# FOC.net
KiCad netlist of a schematic drawn in Altium Designer
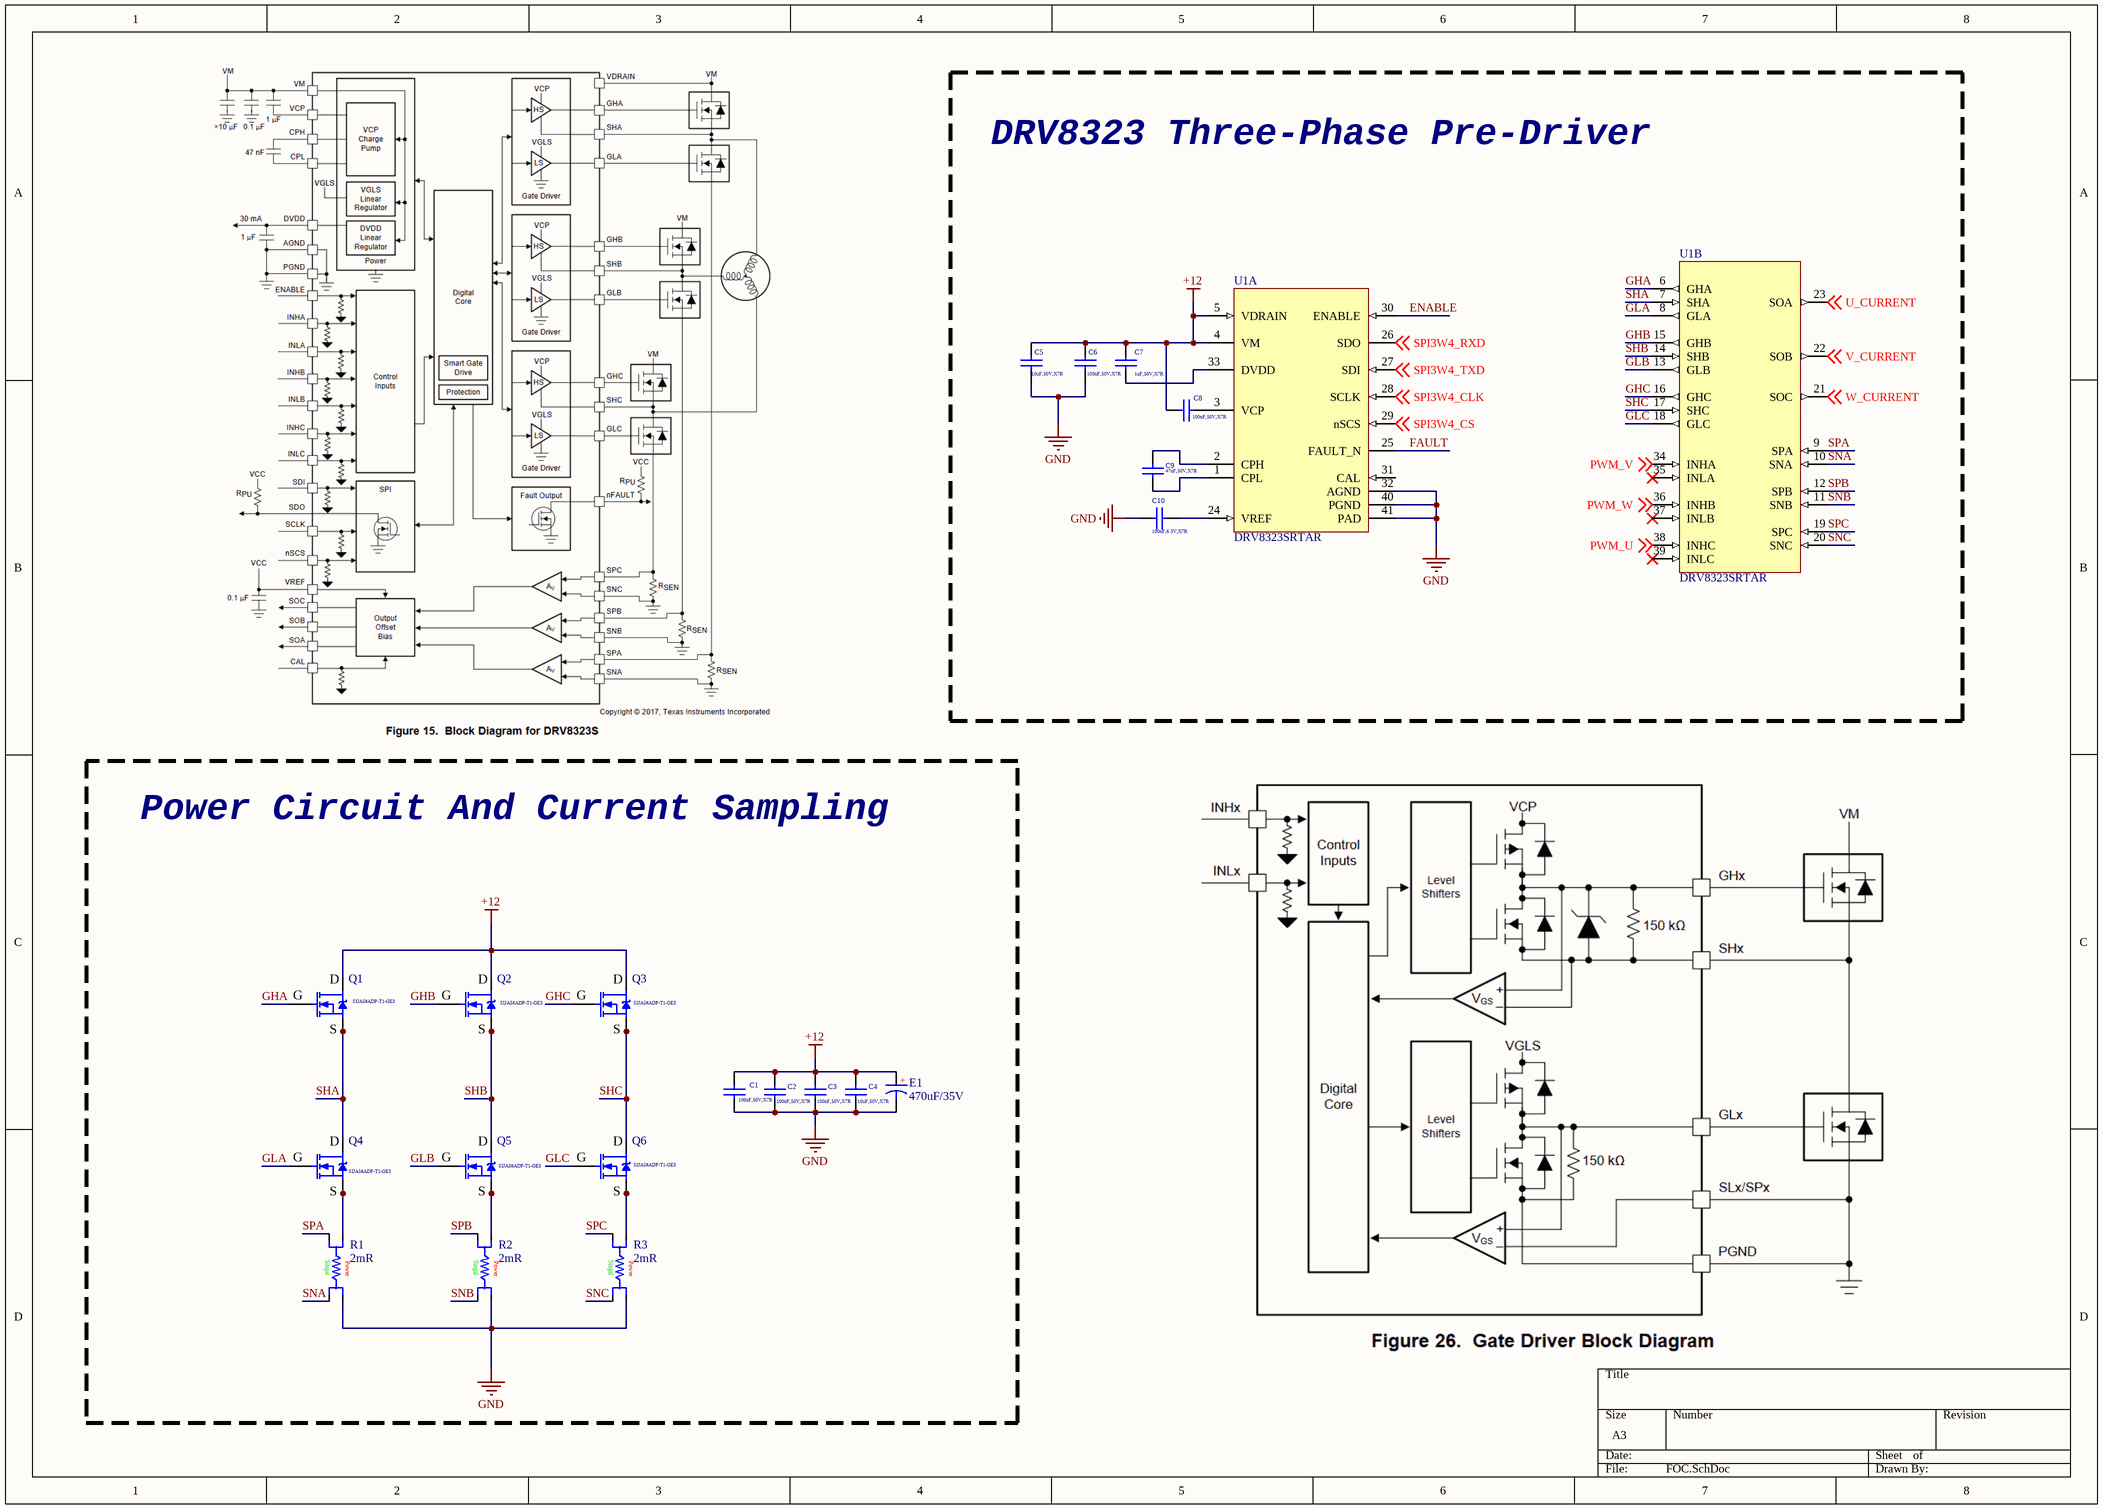
[diagram p0: FOC.SchDoc]

(export (version "E")
  (design (tool "Eeschema 10.0.6"))
  (components
    (comp (ref "C1")
      (value "100nF,50V,X7R")
      (footprint "C0603_L")
      (description "贴片电容/MLCC电容")
      (libsource (lib "0.1 - 电阻-电容-电感-保险丝-晶振-晶体-磁珠-电位器-法拉电容-馈通电容") (part "C"))
    )
    (comp (ref "C2")
      (value "100nF,50V,X7R")
      (footprint "C0603_L")
      (description "贴片电容/MLCC电容")
      (libsource (lib "0.1 - 电阻-电容-电感-保险丝-晶振-晶体-磁珠-电位器-法拉电容-馈通电容") (part "C"))
    )
    (comp (ref "C3")
      (value "100nF,50V,X7R")
      (footprint "C0603_L")
      (description "贴片电容/MLCC电容")
      (libsource (lib "0.1 - 电阻-电容-电感-保险丝-晶振-晶体-磁珠-电位器-法拉电容-馈通电容") (part "C"))
    )
    (comp (ref "C4")
      (value "10uF,50V,X7R")
      (footprint "C0603_L")
      (description "贴片电容/MLCC电容")
      (libsource (lib "0.1 - 电阻-电容-电感-保险丝-晶振-晶体-磁珠-电位器-法拉电容-馈通电容") (part "C"))
    )
    (comp (ref "C5")
      (value "10uF,50V,X7R")
      (footprint "C0402_L")
      (description "贴片电容/MLCC电容")
      (libsource (lib "0.1 - 电阻-电容-电感-保险丝-晶振-晶体-磁珠-电位器-法拉电容-馈通电容") (part "C"))
    )
    (comp (ref "C6")
      (value "100nF,50V,X7R")
      (footprint "C0402_L")
      (description "贴片电容/MLCC电容")
      (libsource (lib "0.1 - 电阻-电容-电感-保险丝-晶振-晶体-磁珠-电位器-法拉电容-馈通电容") (part "C"))
    )
    (comp (ref "C7")
      (value "1uF,50V,X7R")
      (footprint "C0402_L")
      (description "贴片电容/MLCC电容")
      (libsource (lib "0.1 - 电阻-电容-电感-保险丝-晶振-晶体-磁珠-电位器-法拉电容-馈通电容") (part "C"))
    )
    (comp (ref "C8")
      (value "100nF,50V,X7R")
      (footprint "C0402_L")
      (description "贴片电容/MLCC电容")
      (libsource (lib "0.1 - 电阻-电容-电感-保险丝-晶振-晶体-磁珠-电位器-法拉电容-馈通电容") (part "C"))
    )
    (comp (ref "C9")
      (value "47nF,50V,X7R")
      (footprint "C0402_L")
      (description "贴片电容/MLCC电容")
      (libsource (lib "0.1 - 电阻-电容-电感-保险丝-晶振-晶体-磁珠-电位器-法拉电容-馈通电容") (part "C"))
    )
    (comp (ref "C10")
      (value "100nF,6.3V,X7R")
      (footprint "C0402_L")
      (description "贴片电容/MLCC电容")
      (libsource (lib "0.1 - 电阻-电容-电感-保险丝-晶振-晶体-磁珠-电位器-法拉电容-馈通电容") (part "C"))
    )
    (comp (ref "E1")
      (value "470uF/35V")
      (footprint "CE E(8*6.2)")
      (description "贴片电解电容")
      (libsource (lib "0.1 - 电阻-电容-电感-保险丝-晶振-晶体-磁珠-电位器-法拉电容-馈通电容") (part "CE_SMD"))
    )
    (comp (ref "Q1")
      (value "SIJA58ADP-T1-GE3")
      (footprint "POWERPAK SO-8L_VIS")
      (description "Power Field-Effect Transistor")
      (libsource (lib "海南大学MECHA战队") (part "SIJA58ADP-T1-GE3"))
    )
    (comp (ref "Q2")
      (value "SIJA58ADP-T1-GE3")
      (footprint "POWERPAK SO-8L_VIS")
      (description "Power Field-Effect Transistor")
      (libsource (lib "海南大学MECHA战队") (part "SIJA58ADP-T1-GE3"))
    )
    (comp (ref "Q3")
      (value "SIJA58ADP-T1-GE3")
      (footprint "POWERPAK SO-8L_VIS")
      (description "Power Field-Effect Transistor")
      (libsource (lib "海南大学MECHA战队") (part "SIJA58ADP-T1-GE3"))
    )
    (comp (ref "Q4")
      (value "SIJA58ADP-T1-GE3")
      (footprint "POWERPAK SO-8L_VIS")
      (description "Power Field-Effect Transistor")
      (libsource (lib "海南大学MECHA战队") (part "SIJA58ADP-T1-GE3"))
    )
    (comp (ref "Q5")
      (value "SIJA58ADP-T1-GE3")
      (footprint "POWERPAK SO-8L_VIS")
      (description "Power Field-Effect Transistor")
      (libsource (lib "海南大学MECHA战队") (part "SIJA58ADP-T1-GE3"))
    )
    (comp (ref "Q6")
      (value "SIJA58ADP-T1-GE3")
      (footprint "POWERPAK SO-8L_VIS")
      (description "Power Field-Effect Transistor")
      (libsource (lib "海南大学MECHA战队") (part "SIJA58ADP-T1-GE3"))
    )
    (comp (ref "R1")
      (value "2mR")
      (footprint "WSKW0612_VIS")
      (description "SMD Chip Resistor, 2 MOhm, ± 1%, 1 W, 0612 [1632 Metric], Metal Strip, High Power")
      (libsource (lib "海南大学MECHA战队") (part "WSKW06122L000FEA"))
    )
    (comp (ref "R2")
      (value "2mR")
      (footprint "WSKW0612_VIS")
      (description "SMD Chip Resistor, 2 MOhm, ± 1%, 1 W, 0612 [1632 Metric], Metal Strip, High Power")
      (libsource (lib "海南大学MECHA战队") (part "WSKW06122L000FEA"))
    )
    (comp (ref "R3")
      (value "2mR")
      (footprint "WSKW0612_VIS")
      (description "SMD Chip Resistor, 2 MOhm, ± 1%, 1 W, 0612 [1632 Metric], Metal Strip, High Power")
      (libsource (lib "海南大学MECHA战队") (part "WSKW06122L000FEA"))
    )
    (comp (ref "U1")
      (value "DRV8323SRTAR")
      (footprint "DRV8323SRTAR-Footprint-1")
      (description "65-V max 3-phase smart gate driver with current shunt amplifiers 40-WQFN -40 to 125")
      (libsource (lib "海南大学MECHA战队") (part "DRV8323SRTAR"))
    )
  )
  (nets
    (net (code "1") (name "+12") (class "Default")
      (node (ref "C1") (pin "1") (pinfunction "1_1") (pintype "passive"))
      (node (ref "C2") (pin "1") (pinfunction "1_1") (pintype "passive"))
      (node (ref "C3") (pin "1") (pinfunction "1_1") (pintype "passive"))
      (node (ref "C4") (pin "1") (pinfunction "1_1") (pintype "passive"))
      (node (ref "C5") (pin "2") (pinfunction "2_2") (pintype "passive"))
      (node (ref "C6") (pin "2") (pinfunction "2_2") (pintype "passive"))
      (node (ref "C7") (pin "1") (pinfunction "1_1") (pintype "passive"))
      (node (ref "C8") (pin "1") (pinfunction "1_1") (pintype "passive"))
      (node (ref "E1") (pin "1") (pinfunction "1_1") (pintype "passive"))
      (node (ref "Q1") (pin "5") (pinfunction "D_5") (pintype "passive"))
      (node (ref "Q2") (pin "5") (pinfunction "D_5") (pintype "passive"))
      (node (ref "Q3") (pin "5") (pinfunction "D_5") (pintype "passive"))
      (node (ref "U1") (pin "4") (pinfunction "VM_4") (pintype "power_in"))
      (node (ref "U1") (pin "5") (pinfunction "VDRAIN_5") (pintype "input"))
    )
    (net (code "2") (name "/ENABLE") (class "Default")
      (node (ref "U1") (pin "30") (pinfunction "ENABLE_30") (pintype "input"))
    )
    (net (code "3") (name "/FAULT") (class "Default")
      (node (ref "U1") (pin "25") (pinfunction "FAULT_N_25") (pintype "open_collector"))
    )
    (net (code "4") (name "/GHA") (class "Default")
      (node (ref "Q1") (pin "4") (pinfunction "G_4") (pintype "passive"))
      (node (ref "U1") (pin "6") (pinfunction "GHA_6") (pintype "output"))
    )
    (net (code "5") (name "/GHB") (class "Default")
      (node (ref "Q2") (pin "4") (pinfunction "G_4") (pintype "passive"))
      (node (ref "U1") (pin "15") (pinfunction "GHB_15") (pintype "output"))
    )
    (net (code "6") (name "/GHC") (class "Default")
      (node (ref "Q3") (pin "4") (pinfunction "G_4") (pintype "passive"))
      (node (ref "U1") (pin "16") (pinfunction "GHC_16") (pintype "output"))
    )
    (net (code "7") (name "/GLA") (class "Default")
      (node (ref "Q4") (pin "4") (pinfunction "G_4") (pintype "passive"))
      (node (ref "U1") (pin "8") (pinfunction "GLA_8") (pintype "output"))
    )
    (net (code "8") (name "/GLB") (class "Default")
      (node (ref "Q5") (pin "4") (pinfunction "G_4") (pintype "passive"))
      (node (ref "U1") (pin "13") (pinfunction "GLB_13") (pintype "output"))
    )
    (net (code "9") (name "/GLC") (class "Default")
      (node (ref "Q6") (pin "4") (pinfunction "G_4") (pintype "passive"))
      (node (ref "U1") (pin "18") (pinfunction "GLC_18") (pintype "output"))
    )
    (net (code "10") (name "/SHA") (class "Default")
      (node (ref "Q1") (pin "1") (pinfunction "S_1") (pintype "passive"))
      (node (ref "Q1") (pin "2") (pinfunction "S_2") (pintype "passive"))
      (node (ref "Q1") (pin "3") (pinfunction "S_3") (pintype "passive"))
      (node (ref "Q4") (pin "5") (pinfunction "D_5") (pintype "passive"))
      (node (ref "U1") (pin "7") (pinfunction "SHA_7") (pintype "input"))
    )
    (net (code "11") (name "/SHB") (class "Default")
      (node (ref "Q2") (pin "1") (pinfunction "S_1") (pintype "passive"))
      (node (ref "Q2") (pin "2") (pinfunction "S_2") (pintype "passive"))
      (node (ref "Q2") (pin "3") (pinfunction "S_3") (pintype "passive"))
      (node (ref "Q5") (pin "5") (pinfunction "D_5") (pintype "passive"))
      (node (ref "U1") (pin "14") (pinfunction "SHB_14") (pintype "input"))
    )
    (net (code "12") (name "/SHC") (class "Default")
      (node (ref "Q3") (pin "1") (pinfunction "S_1") (pintype "passive"))
      (node (ref "Q3") (pin "2") (pinfunction "S_2") (pintype "passive"))
      (node (ref "Q3") (pin "3") (pinfunction "S_3") (pintype "passive"))
      (node (ref "Q6") (pin "5") (pinfunction "D_5") (pintype "passive"))
      (node (ref "U1") (pin "17") (pinfunction "SHC_17") (pintype "input"))
    )
    (net (code "13") (name "/SNA") (class "Default")
      (node (ref "R1") (pin "3") (pinfunction "3_3") (pintype "passive"))
      (node (ref "U1") (pin "10") (pinfunction "SNA_10") (pintype "input"))
    )
    (net (code "14") (name "/SNB") (class "Default")
      (node (ref "R2") (pin "3") (pinfunction "3_3") (pintype "passive"))
      (node (ref "U1") (pin "11") (pinfunction "SNB_11") (pintype "input"))
    )
    (net (code "15") (name "/SNC") (class "Default")
      (node (ref "R3") (pin "3") (pinfunction "3_3") (pintype "passive"))
      (node (ref "U1") (pin "20") (pinfunction "SNC_20") (pintype "input"))
    )
    (net (code "16") (name "/SPA") (class "Default")
      (node (ref "R1") (pin "2") (pinfunction "2_2") (pintype "passive"))
      (node (ref "U1") (pin "9") (pinfunction "SPA_9") (pintype "input"))
    )
    (net (code "17") (name "/SPB") (class "Default")
      (node (ref "R2") (pin "2") (pinfunction "2_2") (pintype "passive"))
      (node (ref "U1") (pin "12") (pinfunction "SPB_12") (pintype "input"))
    )
    (net (code "18") (name "/SPC") (class "Default")
      (node (ref "R3") (pin "2") (pinfunction "2_2") (pintype "passive"))
      (node (ref "U1") (pin "19") (pinfunction "SPC_19") (pintype "input"))
    )
    (net (code "19") (name "GND") (class "Default")
      (node (ref "C1") (pin "2") (pinfunction "2_2") (pintype "passive"))
      (node (ref "C10") (pin "1") (pinfunction "1_1") (pintype "passive"))
      (node (ref "C2") (pin "2") (pinfunction "2_2") (pintype "passive"))
      (node (ref "C3") (pin "2") (pinfunction "2_2") (pintype "passive"))
      (node (ref "C4") (pin "2") (pinfunction "2_2") (pintype "passive"))
      (node (ref "C5") (pin "1") (pinfunction "1_1") (pintype "passive"))
      (node (ref "C6") (pin "1") (pinfunction "1_1") (pintype "passive"))
      (node (ref "E1") (pin "2") (pinfunction "2_2") (pintype "passive"))
      (node (ref "R1") (pin "4") (pinfunction "4_4") (pintype "passive"))
      (node (ref "R2") (pin "4") (pinfunction "4_4") (pintype "passive"))
      (node (ref "R3") (pin "4") (pinfunction "4_4") (pintype "passive"))
      (node (ref "U1") (pin "32") (pinfunction "AGND_32") (pintype "power_in"))
      (node (ref "U1") (pin "40") (pinfunction "PGND_40") (pintype "power_in"))
      (node (ref "U1") (pin "41") (pinfunction "PAD_41") (pintype "power_in"))
    )
    (net (code "20") (name "Net-(Q4-S-Pad1)") (class "Default")
      (node (ref "Q4") (pin "1") (pinfunction "S_1") (pintype "passive"))
      (node (ref "Q4") (pin "2") (pinfunction "S_2") (pintype "passive"))
      (node (ref "Q4") (pin "3") (pinfunction "S_3") (pintype "passive"))
      (node (ref "R1") (pin "1") (pinfunction "1_1") (pintype "passive"))
    )
    (net (code "21") (name "Net-(Q5-S-Pad1)") (class "Default")
      (node (ref "Q5") (pin "1") (pinfunction "S_1") (pintype "passive"))
      (node (ref "Q5") (pin "2") (pinfunction "S_2") (pintype "passive"))
      (node (ref "Q5") (pin "3") (pinfunction "S_3") (pintype "passive"))
      (node (ref "R2") (pin "1") (pinfunction "1_1") (pintype "passive"))
    )
    (net (code "22") (name "Net-(Q6-S-Pad1)") (class "Default")
      (node (ref "Q6") (pin "1") (pinfunction "S_1") (pintype "passive"))
      (node (ref "Q6") (pin "2") (pinfunction "S_2") (pintype "passive"))
      (node (ref "Q6") (pin "3") (pinfunction "S_3") (pintype "passive"))
      (node (ref "R3") (pin "1") (pinfunction "1_1") (pintype "passive"))
    )
    (net (code "23") (name "Net-(U1A-CPH)") (class "Default")
      (node (ref "C9") (pin "1") (pinfunction "1_1") (pintype "passive"))
      (node (ref "U1") (pin "2") (pinfunction "CPH_2") (pintype "passive"))
    )
    (net (code "24") (name "Net-(U1A-CPL)") (class "Default")
      (node (ref "C9") (pin "2") (pinfunction "2_2") (pintype "passive"))
      (node (ref "U1") (pin "1") (pinfunction "CPL_1") (pintype "passive"))
    )
    (net (code "25") (name "Net-(U1A-DVDD)") (class "Default")
      (node (ref "C7") (pin "2") (pinfunction "2_2") (pintype "passive"))
      (node (ref "U1") (pin "33") (pinfunction "DVDD_33") (pintype "power_in"))
    )
    (net (code "26") (name "Net-(U1A-VCP)") (class "Default")
      (node (ref "C8") (pin "2") (pinfunction "2_2") (pintype "passive"))
      (node (ref "U1") (pin "3") (pinfunction "VCP_3") (pintype "power_in"))
    )
    (net (code "27") (name "Net-(U1A-VREF)") (class "Default")
      (node (ref "C10") (pin "2") (pinfunction "2_2") (pintype "passive"))
      (node (ref "U1") (pin "24") (pinfunction "VREF_24") (pintype "input"))
    )
    (net (code "28") (name "PWM_U") (class "Default")
      (node (ref "U1") (pin "38") (pinfunction "INHC_38") (pintype "input"))
    )
    (net (code "29") (name "PWM_V") (class "Default")
      (node (ref "U1") (pin "34") (pinfunction "INHA_34") (pintype "input"))
    )
    (net (code "30") (name "PWM_W") (class "Default")
      (node (ref "U1") (pin "36") (pinfunction "INHB_36") (pintype "input"))
    )
    (net (code "31") (name "SPI3W4_CLK") (class "Default")
      (node (ref "U1") (pin "28") (pinfunction "SCLK_28") (pintype "input"))
    )
    (net (code "32") (name "SPI3W4_CS") (class "Default")
      (node (ref "U1") (pin "29") (pinfunction "nSCS_29") (pintype "input"))
    )
    (net (code "33") (name "SPI3W4_RXD") (class "Default")
      (node (ref "U1") (pin "26") (pinfunction "SDO_26") (pintype "passive"))
    )
    (net (code "34") (name "SPI3W4_TXD") (class "Default")
      (node (ref "U1") (pin "27") (pinfunction "SDI_27") (pintype "input"))
    )
    (net (code "35") (name "U_CURRENT") (class "Default")
      (node (ref "U1") (pin "23") (pinfunction "SOA_23") (pintype "output"))
    )
    (net (code "36") (name "V_CURRENT") (class "Default")
      (node (ref "U1") (pin "22") (pinfunction "SOB_22") (pintype "output"))
    )
    (net (code "37") (name "W_CURRENT") (class "Default")
      (node (ref "U1") (pin "21") (pinfunction "SOC_21") (pintype "output"))
    )
    (net (code "38") (name "unconnected-(U1A-CAL-Pad31)") (class "Default")
      (node (ref "U1") (pin "31") (pinfunction "CAL_31") (pintype "input"))
    )
    (net (code "39") (name "unconnected-(U1B-INLA-Pad35)") (class "Default")
      (node (ref "U1") (pin "35") (pinfunction "INLA_35") (pintype "input+no_connect"))
    )
    (net (code "40") (name "unconnected-(U1B-INLB-Pad37)") (class "Default")
      (node (ref "U1") (pin "37") (pinfunction "INLB_37") (pintype "input+no_connect"))
    )
    (net (code "41") (name "unconnected-(U1B-INLC-Pad39)") (class "Default")
      (node (ref "U1") (pin "39") (pinfunction "INLC_39") (pintype "input+no_connect"))
    )
  )
)
